# Ultrasonic_HC-SR04.net
KiCad netlist of a schematic drawn in Altium Designer
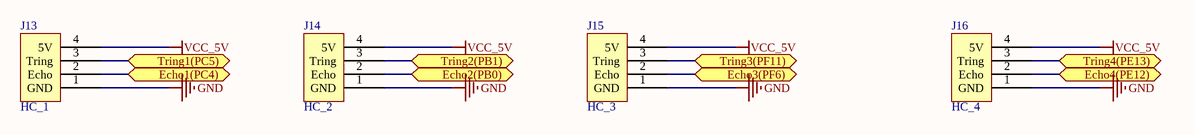
[diagram p0: Ultrasonic_HC-SR04.SchDoc]

(export (version "E")
  (design (tool "Eeschema 10.0.6"))
  (components
    (comp (ref "J13")
      (value "HC_1")
      (footprint "XH2.54-WI-4P")
      (libsource (lib "ZH1.5") (part "Component_5"))
    )
    (comp (ref "J14")
      (value "HC_2")
      (footprint "XH2.54-WI-4P")
      (libsource (lib "ZH1.5") (part "Component_5"))
    )
    (comp (ref "J15")
      (value "HC_3")
      (footprint "XH2.54-WI-4P")
      (libsource (lib "ZH1.5") (part "Component_5"))
    )
    (comp (ref "J16")
      (value "HC_4")
      (footprint "XH2.54-WI-4P")
      (libsource (lib "ZH1.5") (part "Component_5"))
    )
  )
  (nets
    (net (code "1") (name "/Echo1(PC4)") (class "Default")
      (node (ref "J13") (pin "2") (pinfunction "Echo_2") (pintype "passive"))
    )
    (net (code "2") (name "/Echo2(PB0)") (class "Default")
      (node (ref "J14") (pin "2") (pinfunction "Echo_2") (pintype "passive"))
    )
    (net (code "3") (name "/Echo3(PF6)") (class "Default")
      (node (ref "J15") (pin "2") (pinfunction "Echo_2") (pintype "passive"))
    )
    (net (code "4") (name "/Echo4(PE12)") (class "Default")
      (node (ref "J16") (pin "2") (pinfunction "Echo_2") (pintype "passive"))
    )
    (net (code "5") (name "/Tring1(PC5)") (class "Default")
      (node (ref "J13") (pin "3") (pinfunction "Tring_3") (pintype "passive"))
    )
    (net (code "6") (name "/Tring2(PB1)") (class "Default")
      (node (ref "J14") (pin "3") (pinfunction "Tring_3") (pintype "passive"))
    )
    (net (code "7") (name "/Tring3(PF11)") (class "Default")
      (node (ref "J15") (pin "3") (pinfunction "Tring_3") (pintype "passive"))
    )
    (net (code "8") (name "/Tring4(PE13)") (class "Default")
      (node (ref "J16") (pin "3") (pinfunction "Tring_3") (pintype "passive"))
    )
    (net (code "9") (name "GND") (class "Default")
      (node (ref "J13") (pin "1") (pinfunction "GND_1") (pintype "passive"))
      (node (ref "J14") (pin "1") (pinfunction "GND_1") (pintype "passive"))
      (node (ref "J15") (pin "1") (pinfunction "GND_1") (pintype "passive"))
      (node (ref "J16") (pin "1") (pinfunction "GND_1") (pintype "passive"))
    )
    (net (code "10") (name "VCC_5V") (class "Default")
      (node (ref "J13") (pin "4") (pinfunction "5V_4") (pintype "passive"))
      (node (ref "J14") (pin "4") (pinfunction "5V_4") (pintype "passive"))
      (node (ref "J15") (pin "4") (pinfunction "5V_4") (pintype "passive"))
      (node (ref "J16") (pin "4") (pinfunction "5V_4") (pintype "passive"))
    )
  )
)
